# 04_Button.net
KiCad netlist of a schematic drawn in Altium Designer
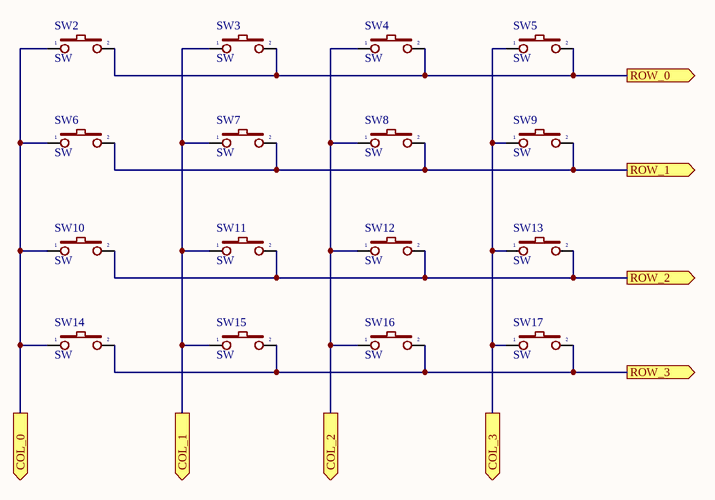
[diagram p0: [04] Button.SchDoc]

(export (version "E")
  (design (tool "Eeschema 10.0.6"))
  (components
    (comp (ref "SW2")
      (value "SW")
      (footprint "SW2")
      (description "Switch button 2 pin")
      (libsource (lib "My Library") (part "SW2"))
    )
    (comp (ref "SW3")
      (value "SW")
      (footprint "SW2")
      (description "Switch button 2 pin")
      (libsource (lib "My Library") (part "SW2"))
    )
    (comp (ref "SW4")
      (value "SW")
      (footprint "SW2")
      (description "Switch button 2 pin")
      (libsource (lib "My Library") (part "SW2"))
    )
    (comp (ref "SW5")
      (value "SW")
      (footprint "SW2")
      (description "Switch button 2 pin")
      (libsource (lib "My Library") (part "SW2"))
    )
    (comp (ref "SW6")
      (value "SW")
      (footprint "SW2")
      (description "Switch button 2 pin")
      (libsource (lib "My Library") (part "SW2"))
    )
    (comp (ref "SW7")
      (value "SW")
      (footprint "SW2")
      (description "Switch button 2 pin")
      (libsource (lib "My Library") (part "SW2"))
    )
    (comp (ref "SW8")
      (value "SW")
      (footprint "SW2")
      (description "Switch button 2 pin")
      (libsource (lib "My Library") (part "SW2"))
    )
    (comp (ref "SW9")
      (value "SW")
      (footprint "SW2")
      (description "Switch button 2 pin")
      (libsource (lib "My Library") (part "SW2"))
    )
    (comp (ref "SW10")
      (value "SW")
      (footprint "SW2")
      (description "Switch button 2 pin")
      (libsource (lib "My Library") (part "SW2"))
    )
    (comp (ref "SW11")
      (value "SW")
      (footprint "SW2")
      (description "Switch button 2 pin")
      (libsource (lib "My Library") (part "SW2"))
    )
    (comp (ref "SW12")
      (value "SW")
      (footprint "SW2")
      (description "Switch button 2 pin")
      (libsource (lib "My Library") (part "SW2"))
    )
    (comp (ref "SW13")
      (value "SW")
      (footprint "SW2")
      (description "Switch button 2 pin")
      (libsource (lib "My Library") (part "SW2"))
    )
    (comp (ref "SW14")
      (value "SW")
      (footprint "SW2")
      (description "Switch button 2 pin")
      (libsource (lib "My Library") (part "SW2"))
    )
    (comp (ref "SW15")
      (value "SW")
      (footprint "SW2")
      (description "Switch button 2 pin")
      (libsource (lib "My Library") (part "SW2"))
    )
    (comp (ref "SW16")
      (value "SW")
      (footprint "SW2")
      (description "Switch button 2 pin")
      (libsource (lib "My Library") (part "SW2"))
    )
    (comp (ref "SW17")
      (value "SW")
      (footprint "SW2")
      (description "Switch button 2 pin")
      (libsource (lib "My Library") (part "SW2"))
    )
  )
  (nets
    (net (code "1") (name "/COL_0") (class "Default")
      (node (ref "SW10") (pin "1") (pinfunction "1_1") (pintype "passive"))
      (node (ref "SW14") (pin "1") (pinfunction "1_1") (pintype "passive"))
      (node (ref "SW2") (pin "1") (pinfunction "1_1") (pintype "passive"))
      (node (ref "SW6") (pin "1") (pinfunction "1_1") (pintype "passive"))
    )
    (net (code "2") (name "/COL_1") (class "Default")
      (node (ref "SW11") (pin "1") (pinfunction "1_1") (pintype "passive"))
      (node (ref "SW15") (pin "1") (pinfunction "1_1") (pintype "passive"))
      (node (ref "SW3") (pin "1") (pinfunction "1_1") (pintype "passive"))
      (node (ref "SW7") (pin "1") (pinfunction "1_1") (pintype "passive"))
    )
    (net (code "3") (name "/COL_2") (class "Default")
      (node (ref "SW12") (pin "1") (pinfunction "1_1") (pintype "passive"))
      (node (ref "SW16") (pin "1") (pinfunction "1_1") (pintype "passive"))
      (node (ref "SW4") (pin "1") (pinfunction "1_1") (pintype "passive"))
      (node (ref "SW8") (pin "1") (pinfunction "1_1") (pintype "passive"))
    )
    (net (code "4") (name "/COL_3") (class "Default")
      (node (ref "SW13") (pin "1") (pinfunction "1_1") (pintype "passive"))
      (node (ref "SW17") (pin "1") (pinfunction "1_1") (pintype "passive"))
      (node (ref "SW5") (pin "1") (pinfunction "1_1") (pintype "passive"))
      (node (ref "SW9") (pin "1") (pinfunction "1_1") (pintype "passive"))
    )
    (net (code "5") (name "/ROW_0") (class "Default")
      (node (ref "SW2") (pin "2") (pinfunction "2_2") (pintype "passive"))
      (node (ref "SW3") (pin "2") (pinfunction "2_2") (pintype "passive"))
      (node (ref "SW4") (pin "2") (pinfunction "2_2") (pintype "passive"))
      (node (ref "SW5") (pin "2") (pinfunction "2_2") (pintype "passive"))
    )
    (net (code "6") (name "/ROW_1") (class "Default")
      (node (ref "SW6") (pin "2") (pinfunction "2_2") (pintype "passive"))
      (node (ref "SW7") (pin "2") (pinfunction "2_2") (pintype "passive"))
      (node (ref "SW8") (pin "2") (pinfunction "2_2") (pintype "passive"))
      (node (ref "SW9") (pin "2") (pinfunction "2_2") (pintype "passive"))
    )
    (net (code "7") (name "/ROW_2") (class "Default")
      (node (ref "SW10") (pin "2") (pinfunction "2_2") (pintype "passive"))
      (node (ref "SW11") (pin "2") (pinfunction "2_2") (pintype "passive"))
      (node (ref "SW12") (pin "2") (pinfunction "2_2") (pintype "passive"))
      (node (ref "SW13") (pin "2") (pinfunction "2_2") (pintype "passive"))
    )
    (net (code "8") (name "/ROW_3") (class "Default")
      (node (ref "SW14") (pin "2") (pinfunction "2_2") (pintype "passive"))
      (node (ref "SW15") (pin "2") (pinfunction "2_2") (pintype "passive"))
      (node (ref "SW16") (pin "2") (pinfunction "2_2") (pintype "passive"))
      (node (ref "SW17") (pin "2") (pinfunction "2_2") (pintype "passive"))
    )
  )
)
